# MainBoard_interface.net
KiCad netlist of a schematic drawn in Altium Designer
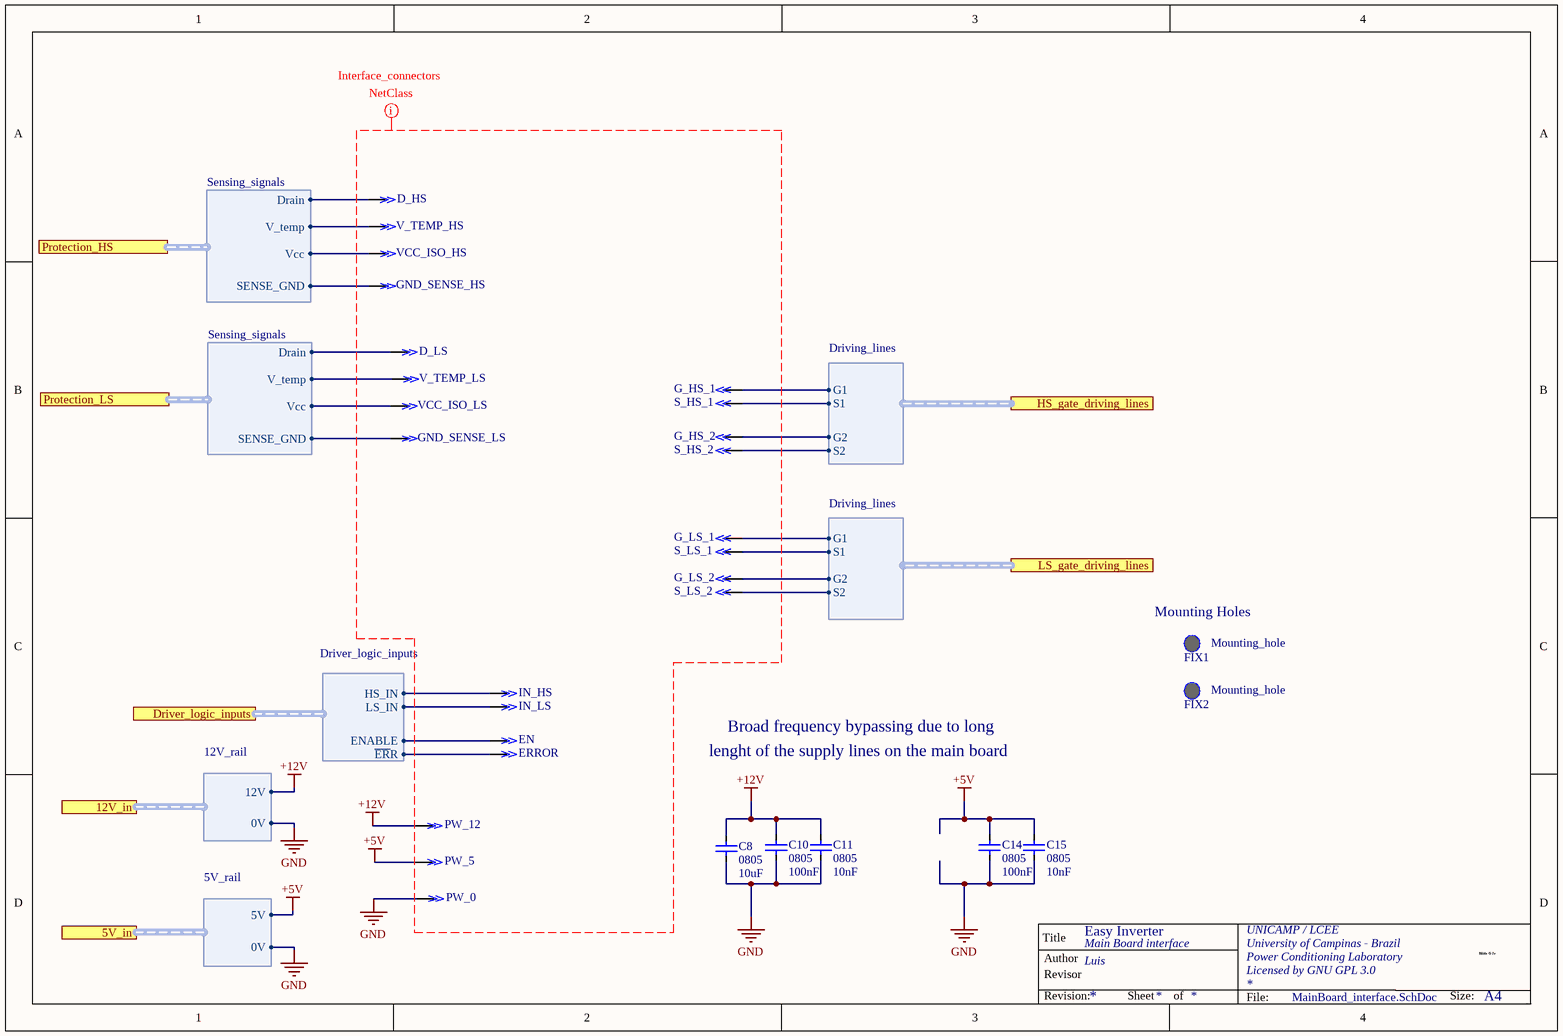
[diagram p0: MainBoard_interface.SchDoc]

(export (version "E")
  (design (tool "Eeschema 10.0.6"))
  (components
    (comp (ref "C8")
      (value "0805")
      (footprint "Capacitor 0805")
      (description "SMD ceramic capacitor 0805")
      (fields (field (name "ALTIUM_VALUE") "10uF"))
      (libsource (lib "EdgeInverter_library") (part "Capacitor 0805"))
    )
    (comp (ref "C10")
      (value "0805")
      (footprint "Capacitor 0805")
      (description "SMD ceramic capacitor 0805")
      (fields (field (name "ALTIUM_VALUE") "100nF"))
      (libsource (lib "EdgeInverter_library") (part "Capacitor 0805"))
    )
    (comp (ref "C11")
      (value "0805")
      (footprint "Capacitor 0805")
      (description "SMD ceramic capacitor 0805")
      (fields (field (name "ALTIUM_VALUE") "10nF"))
      (libsource (lib "EdgeInverter_library") (part "Capacitor 0805"))
    )
    (comp (ref "C14")
      (value "0805")
      (footprint "Capacitor 0805")
      (description "SMD ceramic capacitor 0805")
      (fields (field (name "ALTIUM_VALUE") "100nF"))
      (libsource (lib "EdgeInverter_library") (part "Capacitor 0805"))
    )
    (comp (ref "C15")
      (value "0805")
      (footprint "Capacitor 0805")
      (description "SMD ceramic capacitor 0805")
      (fields (field (name "ALTIUM_VALUE") "10nF"))
      (libsource (lib "EdgeInverter_library") (part "Capacitor 0805"))
    )
    (comp (ref "D_HS")
      (value "Board interconection")
      (footprint "Single pad - Right Angle")
      (description "Interconection between gatedriver and main board")
      (libsource (lib "EdgeInverter_library") (part "Board interconection"))
    )
    (comp (ref "D_LS")
      (value "Board interconection")
      (footprint "Single pad - Right Angle")
      (description "Interconection between gatedriver and main board")
      (libsource (lib "EdgeInverter_library") (part "Board interconection"))
    )
    (comp (ref "EN")
      (value "Board interconection")
      (footprint "Single pad - Right Angle")
      (description "Interconection between gatedriver and main board")
      (libsource (lib "EdgeInverter_library") (part "Board interconection"))
    )
    (comp (ref "ERROR")
      (value "Board interconection")
      (footprint "Single pad - Right Angle")
      (description "Interconection between gatedriver and main board")
      (libsource (lib "EdgeInverter_library") (part "Board interconection"))
    )
    (comp (ref "FIX1")
      (value "Mounting_hole")
      (footprint "Mounting Hole - GateDriver-Right Angle")
      (description "Mount Hole, to interface MainBoard with GatedriverBoard or MainBoard with heatsink")
      (libsource (lib "EdgeInverter_library") (part "Mounting_hole"))
    )
    (comp (ref "FIX2")
      (value "Mounting_hole")
      (footprint "Mounting Hole - GateDriver-Right Angle")
      (description "Mount Hole, to interface MainBoard with GatedriverBoard or MainBoard with heatsink")
      (libsource (lib "EdgeInverter_library") (part "Mounting_hole"))
    )
    (comp (ref "GND_SENSE_HS")
      (value "Board interconection")
      (footprint "Single pad - Right Angle")
      (description "Interconection between gatedriver and main board")
      (libsource (lib "EdgeInverter_library") (part "Board interconection"))
    )
    (comp (ref "GND_SENSE_LS")
      (value "Board interconection")
      (footprint "Single pad - Right Angle")
      (description "Interconection between gatedriver and main board")
      (libsource (lib "EdgeInverter_library") (part "Board interconection"))
    )
    (comp (ref "G_HS_1")
      (value "Board interconection")
      (footprint "Single pad - Right Angle")
      (description "Interconection between gatedriver and main board")
      (libsource (lib "EdgeInverter_library") (part "Board interconection"))
    )
    (comp (ref "G_HS_2")
      (value "Board interconection")
      (footprint "Single pad - Right Angle")
      (description "Interconection between gatedriver and main board")
      (libsource (lib "EdgeInverter_library") (part "Board interconection"))
    )
    (comp (ref "G_LS_1")
      (value "Board interconection")
      (footprint "Single pad - Right Angle")
      (description "Interconection between gatedriver and main board")
      (libsource (lib "EdgeInverter_library") (part "Board interconection"))
    )
    (comp (ref "G_LS_2")
      (value "Board interconection")
      (footprint "Single pad - Right Angle")
      (description "Interconection between gatedriver and main board")
      (libsource (lib "EdgeInverter_library") (part "Board interconection"))
    )
    (comp (ref "IN_HS")
      (value "Board interconection")
      (footprint "Single pad - Right Angle")
      (description "Interconection between gatedriver and main board")
      (libsource (lib "EdgeInverter_library") (part "Board interconection"))
    )
    (comp (ref "IN_LS")
      (value "Board interconection")
      (footprint "Single pad - Right Angle")
      (description "Interconection between gatedriver and main board")
      (libsource (lib "EdgeInverter_library") (part "Board interconection"))
    )
    (comp (ref "PW_0")
      (value "Board interconection")
      (footprint "Single pad - Right Angle")
      (description "Interconection between gatedriver and main board")
      (libsource (lib "EdgeInverter_library") (part "Board interconection"))
    )
    (comp (ref "PW_5")
      (value "Board interconection")
      (footprint "Single pad - Right Angle")
      (description "Interconection between gatedriver and main board")
      (libsource (lib "EdgeInverter_library") (part "Board interconection"))
    )
    (comp (ref "PW_12")
      (value "Board interconection")
      (footprint "Single pad - Right Angle")
      (description "Interconection between gatedriver and main board")
      (libsource (lib "EdgeInverter_library") (part "Board interconection"))
    )
    (comp (ref "S_HS_1")
      (value "Board interconection")
      (footprint "Single pad - Right Angle")
      (description "Interconection between gatedriver and main board")
      (libsource (lib "EdgeInverter_library") (part "Board interconection"))
    )
    (comp (ref "S_HS_2")
      (value "Board interconection")
      (footprint "Single pad - Right Angle")
      (description "Interconection between gatedriver and main board")
      (libsource (lib "EdgeInverter_library") (part "Board interconection"))
    )
    (comp (ref "S_LS_1")
      (value "Board interconection")
      (footprint "Single pad - Right Angle")
      (description "Interconection between gatedriver and main board")
      (libsource (lib "EdgeInverter_library") (part "Board interconection"))
    )
    (comp (ref "S_LS_2")
      (value "Board interconection")
      (footprint "Single pad - Right Angle")
      (description "Interconection between gatedriver and main board")
      (libsource (lib "EdgeInverter_library") (part "Board interconection"))
    )
    (comp (ref "VCC_ISO_HS")
      (value "Board interconection")
      (footprint "Single pad - Right Angle")
      (description "Interconection between gatedriver and main board")
      (libsource (lib "EdgeInverter_library") (part "Board interconection"))
    )
    (comp (ref "VCC_ISO_LS")
      (value "Board interconection")
      (footprint "Single pad - Right Angle")
      (description "Interconection between gatedriver and main board")
      (libsource (lib "EdgeInverter_library") (part "Board interconection"))
    )
    (comp (ref "V_TEMP_HS")
      (value "Board interconection")
      (footprint "Single pad - Right Angle")
      (description "Interconection between gatedriver and main board")
      (libsource (lib "EdgeInverter_library") (part "Board interconection"))
    )
    (comp (ref "V_TEMP_LS")
      (value "Board interconection")
      (footprint "Single pad - Right Angle")
      (description "Interconection between gatedriver and main board")
      (libsource (lib "EdgeInverter_library") (part "Board interconection"))
    )
  )
  (nets
    (net (code "6") (name "+5V") (class "Default")
      (node (ref "C14") (pin "1") (pinfunction "1_1") (pintype "passive"))
      (node (ref "C15") (pin "1") (pinfunction "1_1") (pintype "passive"))
      (node (ref "PW_5") (pin "1") (pinfunction "1_1") (pintype "passive"))
    )
    (net (code "7") (name "+12V") (class "Default")
      (node (ref "C10") (pin "1") (pinfunction "1_1") (pintype "passive"))
      (node (ref "C11") (pin "1") (pinfunction "1_1") (pintype "passive"))
      (node (ref "C8") (pin "1") (pinfunction "1_1") (pintype "passive"))
      (node (ref "PW_12") (pin "1") (pinfunction "1_1") (pintype "passive"))
    )
    (net (code "8") (name "/ENABLE") (class "Default")
      (node (ref "EN") (pin "1") (pinfunction "1_1") (pintype "passive"))
    )
    (net (code "9") (name "/HS_IN") (class "Default")
      (node (ref "IN_HS") (pin "1") (pinfunction "1_1") (pintype "passive"))
    )
    (net (code "10") (name "/LS_IN") (class "Default")
      (node (ref "IN_LS") (pin "1") (pinfunction "1_1") (pintype "passive"))
    )
    (net (code "16") (name "/~{ER}R") (class "Default")
      (node (ref "ERROR") (pin "1") (pinfunction "1_1") (pintype "passive"))
    )
    (net (code "17") (name "GND") (class "Default")
      (node (ref "C10") (pin "2") (pinfunction "2_2") (pintype "passive"))
      (node (ref "C11") (pin "2") (pinfunction "2_2") (pintype "passive"))
      (node (ref "C14") (pin "2") (pinfunction "2_2") (pintype "passive"))
      (node (ref "C15") (pin "2") (pinfunction "2_2") (pintype "passive"))
      (node (ref "C8") (pin "2") (pinfunction "2_2") (pintype "passive"))
      (node (ref "PW_0") (pin "1") (pinfunction "1_1") (pintype "passive"))
    )
    (net (code "18") (name "unconnected-(D_HS-Pad1)") (class "Default")
      (node (ref "D_HS") (pin "1") (pinfunction "1_1") (pintype "passive"))
    )
    (net (code "19") (name "unconnected-(D_LS-Pad1)") (class "Default")
      (node (ref "D_LS") (pin "1") (pinfunction "1_1") (pintype "passive"))
    )
    (net (code "20") (name "unconnected-(GND_SENSE_HS-Pad1)") (class "Default")
      (node (ref "GND_SENSE_HS") (pin "1") (pinfunction "1_1") (pintype "passive"))
    )
    (net (code "21") (name "unconnected-(GND_SENSE_LS-Pad1)") (class "Default")
      (node (ref "GND_SENSE_LS") (pin "1") (pinfunction "1_1") (pintype "passive"))
    )
    (net (code "22") (name "unconnected-(G_HS_1-Pad1)") (class "Default")
      (node (ref "G_HS_1") (pin "1") (pinfunction "1_1") (pintype "passive"))
    )
    (net (code "23") (name "unconnected-(G_HS_2-Pad1)") (class "Default")
      (node (ref "G_HS_2") (pin "1") (pinfunction "1_1") (pintype "passive"))
    )
    (net (code "24") (name "unconnected-(G_LS_1-Pad1)") (class "Default")
      (node (ref "G_LS_1") (pin "1") (pinfunction "1_1") (pintype "passive"))
    )
    (net (code "25") (name "unconnected-(G_LS_2-Pad1)") (class "Default")
      (node (ref "G_LS_2") (pin "1") (pinfunction "1_1") (pintype "passive"))
    )
    (net (code "26") (name "unconnected-(S_HS_1-Pad1)") (class "Default")
      (node (ref "S_HS_1") (pin "1") (pinfunction "1_1") (pintype "passive"))
    )
    (net (code "27") (name "unconnected-(S_HS_2-Pad1)") (class "Default")
      (node (ref "S_HS_2") (pin "1") (pinfunction "1_1") (pintype "passive"))
    )
    (net (code "28") (name "unconnected-(S_LS_1-Pad1)") (class "Default")
      (node (ref "S_LS_1") (pin "1") (pinfunction "1_1") (pintype "passive"))
    )
    (net (code "29") (name "unconnected-(S_LS_2-Pad1)") (class "Default")
      (node (ref "S_LS_2") (pin "1") (pinfunction "1_1") (pintype "passive"))
    )
    (net (code "30") (name "unconnected-(VCC_ISO_HS-Pad1)") (class "Default")
      (node (ref "VCC_ISO_HS") (pin "1") (pinfunction "1_1") (pintype "passive"))
    )
    (net (code "31") (name "unconnected-(VCC_ISO_LS-Pad1)") (class "Default")
      (node (ref "VCC_ISO_LS") (pin "1") (pinfunction "1_1") (pintype "passive"))
    )
    (net (code "32") (name "unconnected-(V_TEMP_HS-Pad1)") (class "Default")
      (node (ref "V_TEMP_HS") (pin "1") (pinfunction "1_1") (pintype "passive"))
    )
    (net (code "33") (name "unconnected-(V_TEMP_LS-Pad1)") (class "Default")
      (node (ref "V_TEMP_LS") (pin "1") (pinfunction "1_1") (pintype "passive"))
    )
  )
)
